# Grove_-_Sound_Sensor_v1.net
KiCad netlist of a schematic drawn in EAGLE
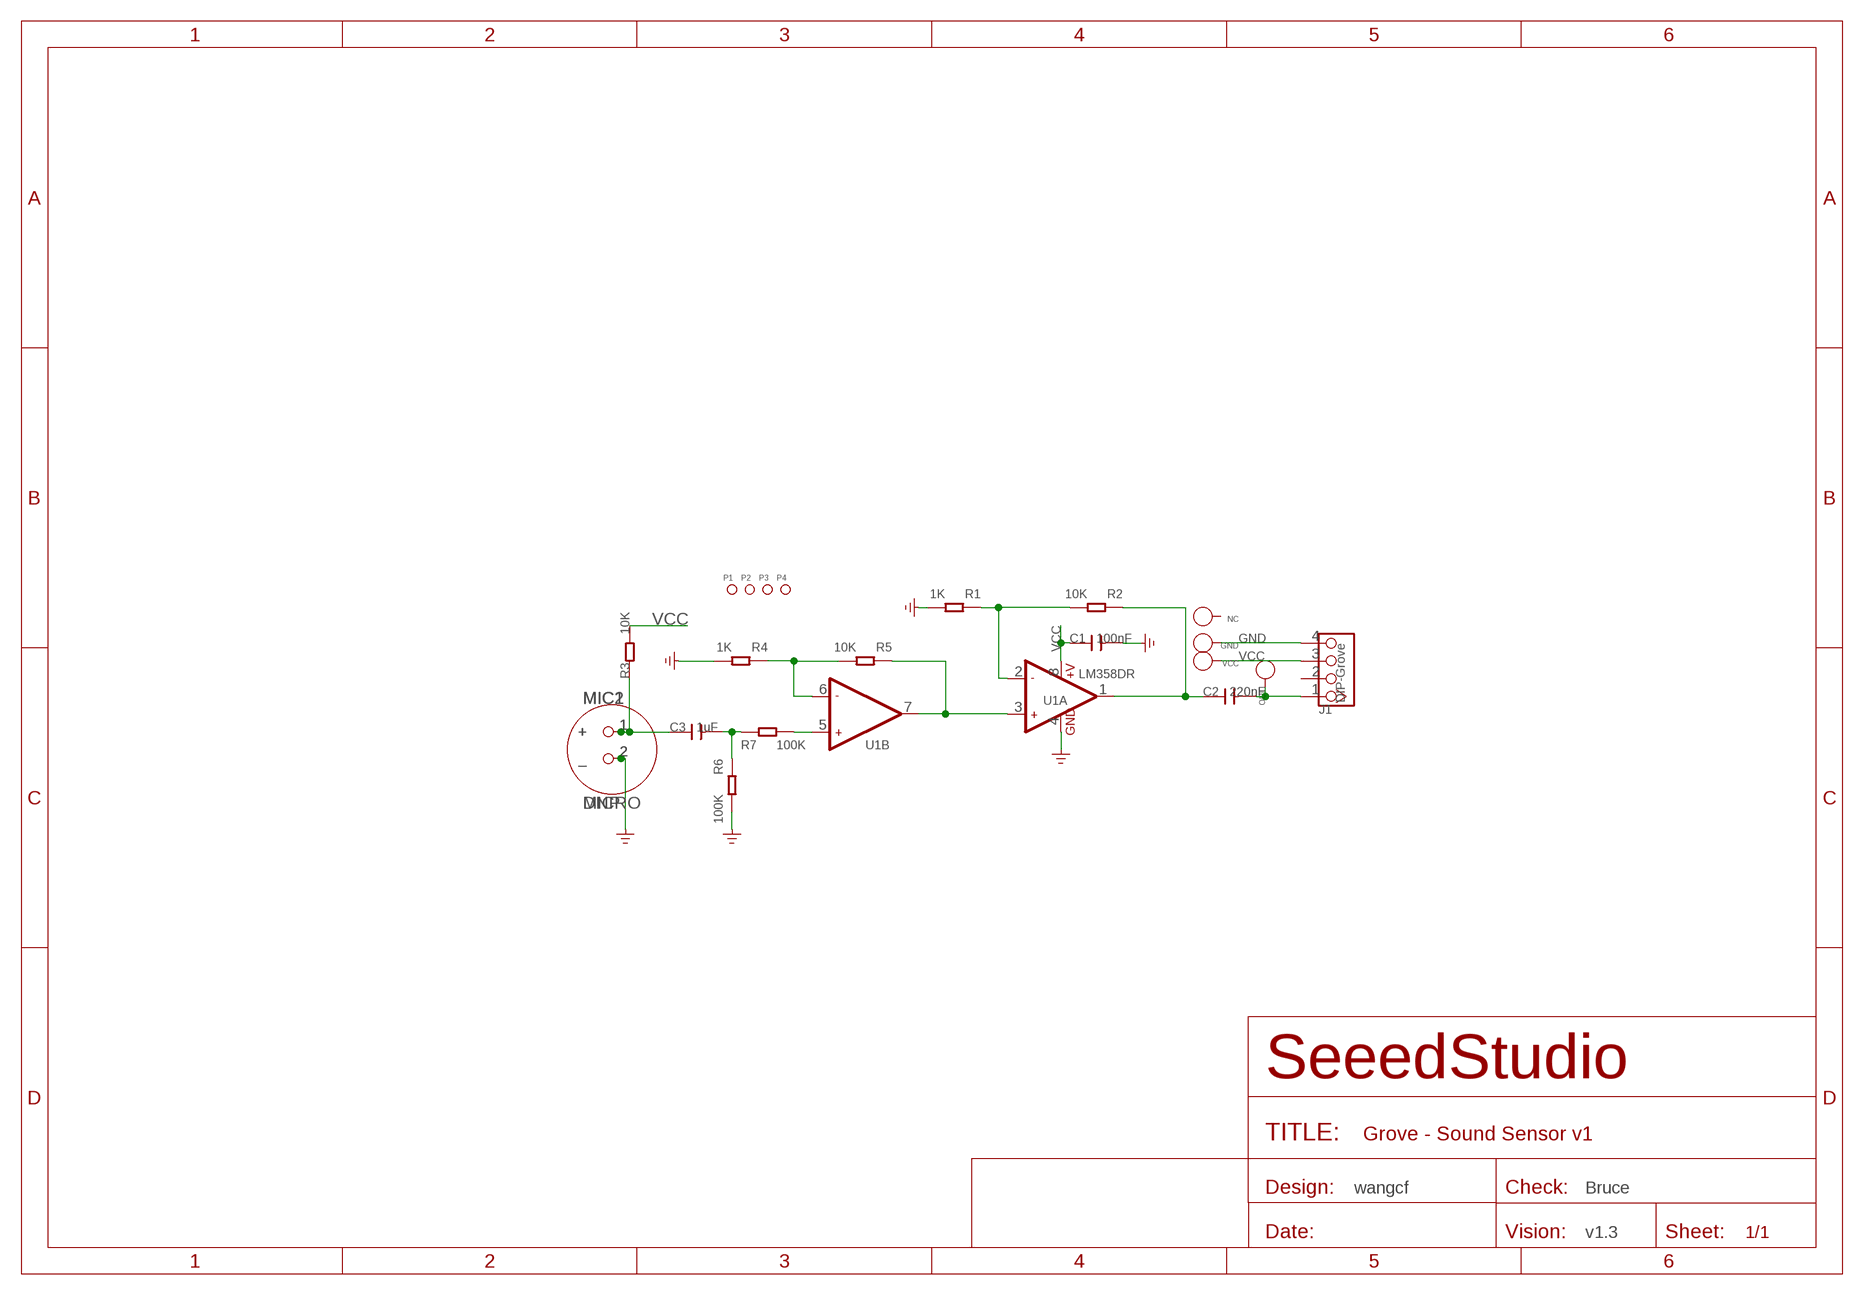
[diagram p0: schematic, sheet 1]

(export (version "E")
  (design (tool "Eeschema 10.0.6"))
  (components
    (comp (ref "C1")
      (value "100nF")
      (footprint "eagle-import:C0603")
      (libsource (lib "eagle-import") (part "C-0603"))
    )
    (comp (ref "C2")
      (value "220nF")
      (footprint "eagle-import:C0603")
      (libsource (lib "eagle-import") (part "C-0603"))
    )
    (comp (ref "C3")
      (value "1uF")
      (footprint "eagle-import:C0603")
      (libsource (lib "eagle-import") (part "C-0603"))
    )
    (comp (ref "GND")
      (value "PAD-TEST-POINT'4545'")
      (footprint "eagle-import:TP_4545")
      (fields (field (name "PARTNO") "DNP"))
      (libsource (lib "eagle-import") (part "PAD-TEST-POINT'4545'"))
    )
    (comp (ref "J1")
      (value "DIP-Grove")
      (footprint "eagle-import:4P-2.0")
      (libsource (lib "eagle-import") (part "TWIG-4P-2.0-2.0"))
    )
    (comp (ref "MIC1")
      (value "MICRO")
      (footprint "eagle-import:MICRO")
      (libsource (lib "eagle-import") (part "MICRO"))
    )
    (comp (ref "MIC2")
      (value "DNP")
      (footprint "eagle-import:MICRO")
      (libsource (lib "eagle-import") (part "MICRO"))
    )
    (comp (ref "NC")
      (value "PAD-TEST-POINT'4545'")
      (footprint "eagle-import:TP_4545")
      (fields (field (name "PARTNO") "DNP"))
      (libsource (lib "eagle-import") (part "PAD-TEST-POINT'4545'"))
    )
    (comp (ref "OUT")
      (value "PAD-TEST-POINT'4545'")
      (footprint "eagle-import:TP_4545")
      (fields (field (name "PARTNO") "DNP"))
      (libsource (lib "eagle-import") (part "PAD-TEST-POINT'4545'"))
    )
    (comp (ref "P1")
      (value "PAD-MARK")
      (footprint "eagle-import:ROUND-MARK-1.0")
      (fields (field (name "PARTNO") "DNP"))
      (libsource (lib "eagle-import") (part "PAD-MARK"))
    )
    (comp (ref "P2")
      (value "PAD-MARK")
      (footprint "eagle-import:ROUND-MARK-1.0")
      (fields (field (name "PARTNO") "DNP"))
      (libsource (lib "eagle-import") (part "PAD-MARK"))
    )
    (comp (ref "P3")
      (value "PAD-MARK")
      (footprint "eagle-import:ROUND-MARK-1.0")
      (fields (field (name "PARTNO") "DNP"))
      (libsource (lib "eagle-import") (part "PAD-MARK"))
    )
    (comp (ref "P4")
      (value "PAD-MARK")
      (footprint "eagle-import:ROUND-MARK-1.0")
      (fields (field (name "PARTNO") "DNP"))
      (libsource (lib "eagle-import") (part "PAD-MARK"))
    )
    (comp (ref "R1")
      (value "1K")
      (footprint "eagle-import:R0603")
      (libsource (lib "eagle-import") (part "R-0603"))
    )
    (comp (ref "R2")
      (value "10K")
      (footprint "eagle-import:R0603")
      (libsource (lib "eagle-import") (part "R-0603"))
    )
    (comp (ref "R3")
      (value "10K")
      (footprint "eagle-import:R0603")
      (libsource (lib "eagle-import") (part "R-0603"))
    )
    (comp (ref "R4")
      (value "1K")
      (footprint "eagle-import:R0603")
      (libsource (lib "eagle-import") (part "R-0603"))
    )
    (comp (ref "R5")
      (value "10K")
      (footprint "eagle-import:R0603")
      (libsource (lib "eagle-import") (part "R-0603"))
    )
    (comp (ref "R6")
      (value "100K")
      (footprint "eagle-import:R0603")
      (libsource (lib "eagle-import") (part "R-0603"))
    )
    (comp (ref "R7")
      (value "100K")
      (footprint "eagle-import:R0603")
      (libsource (lib "eagle-import") (part "R-0603"))
    )
    (comp (ref "U1")
      (value "LM358DR")
      (footprint "eagle-import:SO08")
      (libsource (lib "eagle-import") (part "LMV358D"))
    )
    (comp (ref "VCC")
      (value "PAD-TEST-POINT'4545'")
      (footprint "eagle-import:TP_4545")
      (fields (field (name "PARTNO") "DNP"))
      (libsource (lib "eagle-import") (part "PAD-TEST-POINT'4545'"))
    )
  )
  (nets
    (net (code "1") (name "/VCC") (class "Default")
      (node (ref "C1") (pin "1") (pinfunction "1_1") (pintype "passive"))
      (node (ref "J1") (pin "3") (pinfunction "3_3") (pintype "bidirectional"))
      (node (ref "R3") (pin "2") (pinfunction "2_2") (pintype "passive"))
      (node (ref "U1") (pin "8") (pinfunction "+V_8") (pintype "power_in"))
      (node (ref "VCC") (pin "T") (pinfunction "T_T") (pintype "bidirectional"))
    )
    (net (code "2") (name "GND_POWER") (class "Default")
      (node (ref "C1") (pin "2") (pinfunction "2_2") (pintype "passive"))
      (node (ref "GND") (pin "T") (pinfunction "T_T") (pintype "bidirectional"))
      (node (ref "J1") (pin "4") (pinfunction "4_4") (pintype "bidirectional"))
      (node (ref "MIC1") (pin "2") (pinfunction "__2") (pintype "bidirectional"))
      (node (ref "MIC2") (pin "2") (pinfunction "__2") (pintype "bidirectional"))
      (node (ref "R1") (pin "2") (pinfunction "2_2") (pintype "passive"))
      (node (ref "R4") (pin "2") (pinfunction "2_2") (pintype "passive"))
      (node (ref "R6") (pin "2") (pinfunction "2_2") (pintype "passive"))
      (node (ref "U1") (pin "4") (pinfunction "GND_4") (pintype "power_in"))
    )
    (net (code "3") (name "Net-(C2-Pad2)") (class "Default")
      (node (ref "C2") (pin "2") (pinfunction "2_2") (pintype "passive"))
      (node (ref "J1") (pin "1") (pinfunction "1_1") (pintype "bidirectional"))
      (node (ref "OUT") (pin "T") (pinfunction "T_T") (pintype "bidirectional"))
    )
    (net (code "4") (name "Net-(C3-Pad2)") (class "Default")
      (node (ref "C3") (pin "2") (pinfunction "2_2") (pintype "passive"))
      (node (ref "R6") (pin "1") (pinfunction "1_1") (pintype "passive"))
      (node (ref "R7") (pin "1") (pinfunction "1_1") (pintype "passive"))
    )
    (net (code "5") (name "Net-(MIC1-+)") (class "Default")
      (node (ref "C3") (pin "1") (pinfunction "1_1") (pintype "passive"))
      (node (ref "MIC1") (pin "1") (pinfunction "+_1") (pintype "bidirectional"))
      (node (ref "MIC2") (pin "1") (pinfunction "+_1") (pintype "bidirectional"))
      (node (ref "R3") (pin "1") (pinfunction "1_1") (pintype "passive"))
    )
    (net (code "6") (name "Net-(U1A-+IN1)") (class "Default")
      (node (ref "R5") (pin "1") (pinfunction "1_1") (pintype "passive"))
      (node (ref "U1") (pin "3") (pinfunction "+IN1_3") (pintype "input"))
      (node (ref "U1") (pin "7") (pinfunction "OUT2_7") (pintype "output"))
    )
    (net (code "7") (name "Net-(U1A--IN1)") (class "Default")
      (node (ref "R1") (pin "1") (pinfunction "1_1") (pintype "passive"))
      (node (ref "R2") (pin "2") (pinfunction "2_2") (pintype "passive"))
      (node (ref "U1") (pin "2") (pinfunction "-IN1_2") (pintype "input"))
    )
    (net (code "8") (name "Net-(U1A-OUT1)") (class "Default")
      (node (ref "C2") (pin "1") (pinfunction "1_1") (pintype "passive"))
      (node (ref "R2") (pin "1") (pinfunction "1_1") (pintype "passive"))
      (node (ref "U1") (pin "1") (pinfunction "OUT1_1") (pintype "output"))
    )
    (net (code "9") (name "Net-(U1B-+IN2)") (class "Default")
      (node (ref "R7") (pin "2") (pinfunction "2_2") (pintype "passive"))
      (node (ref "U1") (pin "5") (pinfunction "+IN2_5") (pintype "input"))
    )
    (net (code "10") (name "Net-(U1B--IN2)") (class "Default")
      (node (ref "R4") (pin "1") (pinfunction "1_1") (pintype "passive"))
      (node (ref "R5") (pin "2") (pinfunction "2_2") (pintype "passive"))
      (node (ref "U1") (pin "6") (pinfunction "-IN2_6") (pintype "input"))
    )
    (net (code "11") (name "unconnected-(J1-Pad2)") (class "Default")
      (node (ref "J1") (pin "2") (pinfunction "2_2") (pintype "bidirectional"))
    )
    (net (code "12") (name "unconnected-(NC-PadT)") (class "Default")
      (node (ref "NC") (pin "T") (pinfunction "T_T") (pintype "bidirectional"))
    )
  )
)
